# sensor.net
KiCad netlist of a schematic drawn in EAGLE
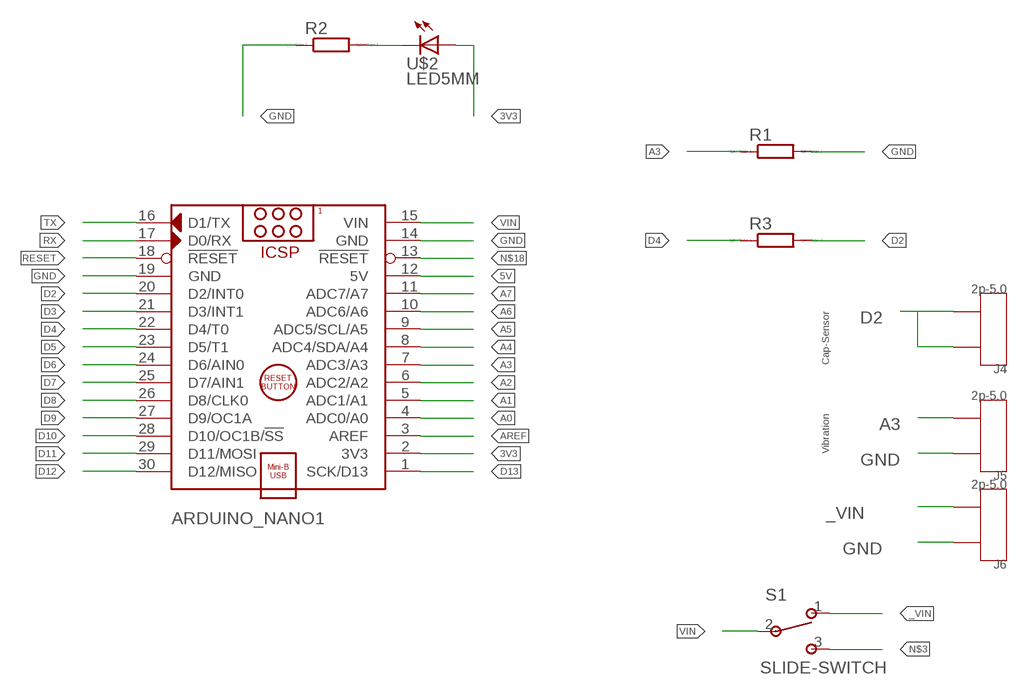
[diagram p0: schematic, sheet 1]

(export (version "E")
  (design (tool "Eeschema 10.0.6"))
  (components
    (comp (ref "ARDUINO_NANO1")
      (value "ARDUINO_NANO")
      (footprint "eagle-import:ARDUINO_NANO")
      (libsource (lib "eagle-import") (part "ARDUINO_NANO"))
    )
    (comp (ref "J4")
      (value "2p-5.0")
      (footprint "eagle-import:H2-5.0")
      (libsource (lib "eagle-import") (part "DIP-FEMALE-BLUE(2P-5.0)"))
    )
    (comp (ref "J5")
      (value "2p-5.0")
      (footprint "eagle-import:H2-5.0")
      (libsource (lib "eagle-import") (part "DIP-FEMALE-BLUE(2P-5.0)"))
    )
    (comp (ref "J6")
      (value "2p-5.0")
      (footprint "eagle-import:H2-5.0")
      (libsource (lib "eagle-import") (part "DIP-FEMALE-BLUE(2P-5.0)"))
    )
    (comp (ref "R1")
      (value "R0204/7")
      (footprint "eagle-import:0204_7")
      (libsource (lib "eagle-import") (part "R0204/7"))
    )
    (comp (ref "R2")
      (value "R0204/7")
      (footprint "eagle-import:0204_7")
      (libsource (lib "eagle-import") (part "R0204/7"))
    )
    (comp (ref "R3")
      (value "R0204/7")
      (footprint "eagle-import:0204_7")
      (libsource (lib "eagle-import") (part "R0204/7"))
    )
    (comp (ref "S1")
      (value "SLIDE-SWITCH")
      (footprint "eagle-import:AYZ0102AGRLC")
      (libsource (lib "eagle-import") (part "SLIDE-SWITCH"))
    )
    (comp (ref "U$2")
      (value "LED5MM")
      (footprint "eagle-import:5MM")
      (libsource (lib "eagle-import") (part "LED5MM"))
    )
  )
  (nets
    (net (code "1") (name "3V3") (class "Default")
      (node (ref "ARDUINO_NANO1") (pin "2") (pinfunction "3V3_2") (pintype "output"))
      (node (ref "U$2") (pin "IN") (pinfunction "A_IN") (pintype "passive"))
    )
    (net (code "2") (name "5V") (class "Default")
      (node (ref "ARDUINO_NANO1") (pin "12") (pinfunction "5V_12") (pintype "power_in"))
    )
    (net (code "3") (name "A0") (class "Default")
      (node (ref "ARDUINO_NANO1") (pin "4") (pinfunction "ADC0/A0_4") (pintype "bidirectional"))
    )
    (net (code "4") (name "A1") (class "Default")
      (node (ref "ARDUINO_NANO1") (pin "5") (pinfunction "ADC1/A1_5") (pintype "bidirectional"))
    )
    (net (code "5") (name "A2") (class "Default")
      (node (ref "ARDUINO_NANO1") (pin "6") (pinfunction "ADC2/A2_6") (pintype "bidirectional"))
    )
    (net (code "6") (name "A3") (class "Default")
      (node (ref "ARDUINO_NANO1") (pin "7") (pinfunction "ADC3/A3_7") (pintype "bidirectional"))
      (node (ref "J5") (pin "2") (pinfunction "P$2_2") (pintype "bidirectional"))
      (node (ref "R1") (pin "1") (pinfunction "1_1") (pintype "passive"))
    )
    (net (code "7") (name "A4") (class "Default")
      (node (ref "ARDUINO_NANO1") (pin "8") (pinfunction "ADC4/SDA/A4_8") (pintype "bidirectional"))
    )
    (net (code "8") (name "A5") (class "Default")
      (node (ref "ARDUINO_NANO1") (pin "9") (pinfunction "ADC5/SCL/A5_9") (pintype "bidirectional"))
    )
    (net (code "9") (name "A6") (class "Default")
      (node (ref "ARDUINO_NANO1") (pin "10") (pinfunction "ADC6/A6_10") (pintype "bidirectional"))
    )
    (net (code "10") (name "A7") (class "Default")
      (node (ref "ARDUINO_NANO1") (pin "11") (pinfunction "ADC7/A7_11") (pintype "bidirectional"))
    )
    (net (code "11") (name "AREF") (class "Default")
      (node (ref "ARDUINO_NANO1") (pin "3") (pinfunction "AREF_3") (pintype "input"))
    )
    (net (code "12") (name "D2") (class "Default")
      (node (ref "ARDUINO_NANO1") (pin "20") (pinfunction "D2/INT0_20") (pintype "bidirectional"))
      (node (ref "J4") (pin "1") (pinfunction "P$1_1") (pintype "bidirectional"))
      (node (ref "J4") (pin "2") (pinfunction "P$2_2") (pintype "bidirectional"))
      (node (ref "R3") (pin "2") (pinfunction "2_2") (pintype "passive"))
    )
    (net (code "13") (name "D3") (class "Default")
      (node (ref "ARDUINO_NANO1") (pin "21") (pinfunction "D3/INT1_21") (pintype "bidirectional"))
    )
    (net (code "14") (name "D4") (class "Default")
      (node (ref "ARDUINO_NANO1") (pin "22") (pinfunction "D4/T0_22") (pintype "bidirectional"))
      (node (ref "R3") (pin "1") (pinfunction "1_1") (pintype "passive"))
    )
    (net (code "15") (name "D5") (class "Default")
      (node (ref "ARDUINO_NANO1") (pin "23") (pinfunction "D5/T1_23") (pintype "bidirectional"))
    )
    (net (code "16") (name "D6") (class "Default")
      (node (ref "ARDUINO_NANO1") (pin "24") (pinfunction "D6/AIN0_24") (pintype "bidirectional"))
    )
    (net (code "17") (name "D7") (class "Default")
      (node (ref "ARDUINO_NANO1") (pin "25") (pinfunction "D7/AIN1_25") (pintype "bidirectional"))
    )
    (net (code "18") (name "D8") (class "Default")
      (node (ref "ARDUINO_NANO1") (pin "26") (pinfunction "D8/CLK0_26") (pintype "bidirectional"))
    )
    (net (code "19") (name "D9") (class "Default")
      (node (ref "ARDUINO_NANO1") (pin "27") (pinfunction "D9/OC1A_27") (pintype "bidirectional"))
    )
    (net (code "20") (name "D10") (class "Default")
      (node (ref "ARDUINO_NANO1") (pin "28") (pinfunction "D10/OC1B/~{SS}_28") (pintype "bidirectional"))
    )
    (net (code "21") (name "D11") (class "Default")
      (node (ref "ARDUINO_NANO1") (pin "29") (pinfunction "D11/MOSI_29") (pintype "bidirectional"))
    )
    (net (code "22") (name "D12") (class "Default")
      (node (ref "ARDUINO_NANO1") (pin "30") (pinfunction "D12/MISO_30") (pintype "bidirectional"))
    )
    (net (code "23") (name "D13") (class "Default")
      (node (ref "ARDUINO_NANO1") (pin "1") (pinfunction "SCK/D13_1") (pintype "bidirectional"))
    )
    (net (code "24") (name "GND") (class "Default")
      (node (ref "ARDUINO_NANO1") (pin "14") (pinfunction "GND_14") (pintype "power_in"))
      (node (ref "ARDUINO_NANO1") (pin "19") (pinfunction "GND_19") (pintype "power_in"))
      (node (ref "J5") (pin "1") (pinfunction "P$1_1") (pintype "bidirectional"))
      (node (ref "J6") (pin "1") (pinfunction "P$1_1") (pintype "bidirectional"))
      (node (ref "R1") (pin "2") (pinfunction "2_2") (pintype "passive"))
      (node (ref "R2") (pin "1") (pinfunction "1_1") (pintype "passive"))
    )
    (net (code "25") (name "N$3") (class "Default")
      (node (ref "S1") (pin "3") (pinfunction "3_3") (pintype "bidirectional"))
    )
    (net (code "26") (name "N$18") (class "Default")
      (node (ref "ARDUINO_NANO1") (pin "13") (pinfunction "~{RESET}_13") (pintype "input"))
    )
    (net (code "27") (name "Net-(U$2-C)") (class "Default")
      (node (ref "R2") (pin "2") (pinfunction "2_2") (pintype "passive"))
      (node (ref "U$2") (pin "OUT") (pinfunction "C_OUT") (pintype "passive"))
    )
    (net (code "28") (name "RESET") (class "Default")
      (node (ref "ARDUINO_NANO1") (pin "18") (pinfunction "~{RESET}_18") (pintype "input"))
    )
    (net (code "29") (name "RX") (class "Default")
      (node (ref "ARDUINO_NANO1") (pin "17") (pinfunction "D0/RX_17") (pintype "bidirectional"))
    )
    (net (code "30") (name "TX") (class "Default")
      (node (ref "ARDUINO_NANO1") (pin "16") (pinfunction "D1/TX_16") (pintype "bidirectional"))
    )
    (net (code "31") (name "VIN") (class "Default")
      (node (ref "ARDUINO_NANO1") (pin "15") (pinfunction "VIN_15") (pintype "power_in"))
      (node (ref "S1") (pin "2") (pinfunction "2_2") (pintype "bidirectional"))
    )
    (net (code "32") (name "_VIN") (class "Default")
      (node (ref "J6") (pin "2") (pinfunction "P$2_2") (pintype "bidirectional"))
      (node (ref "S1") (pin "1") (pinfunction "1_1") (pintype "bidirectional"))
    )
  )
)
